# ase_flap.net
KiCad netlist of a schematic drawn in Altium Designer
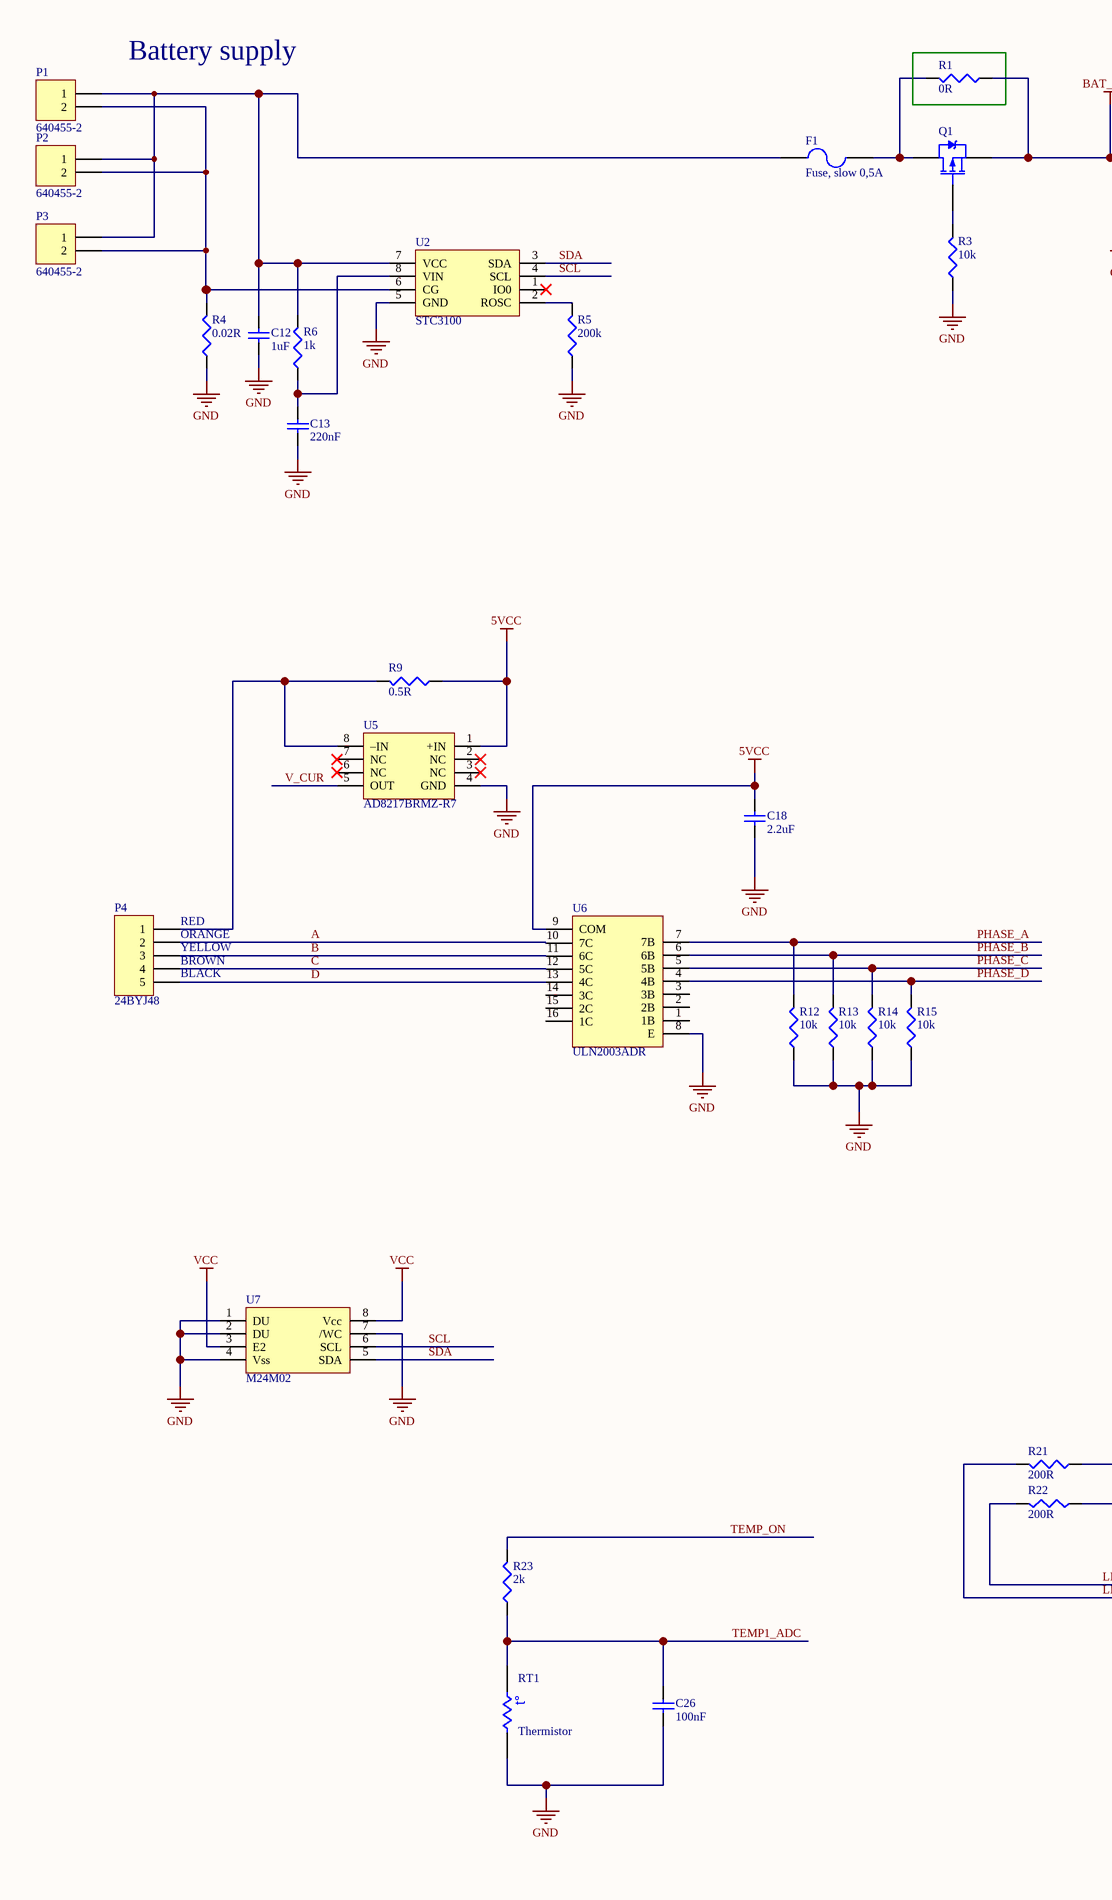
[diagram p0: ase_flap.SchDoc, left]
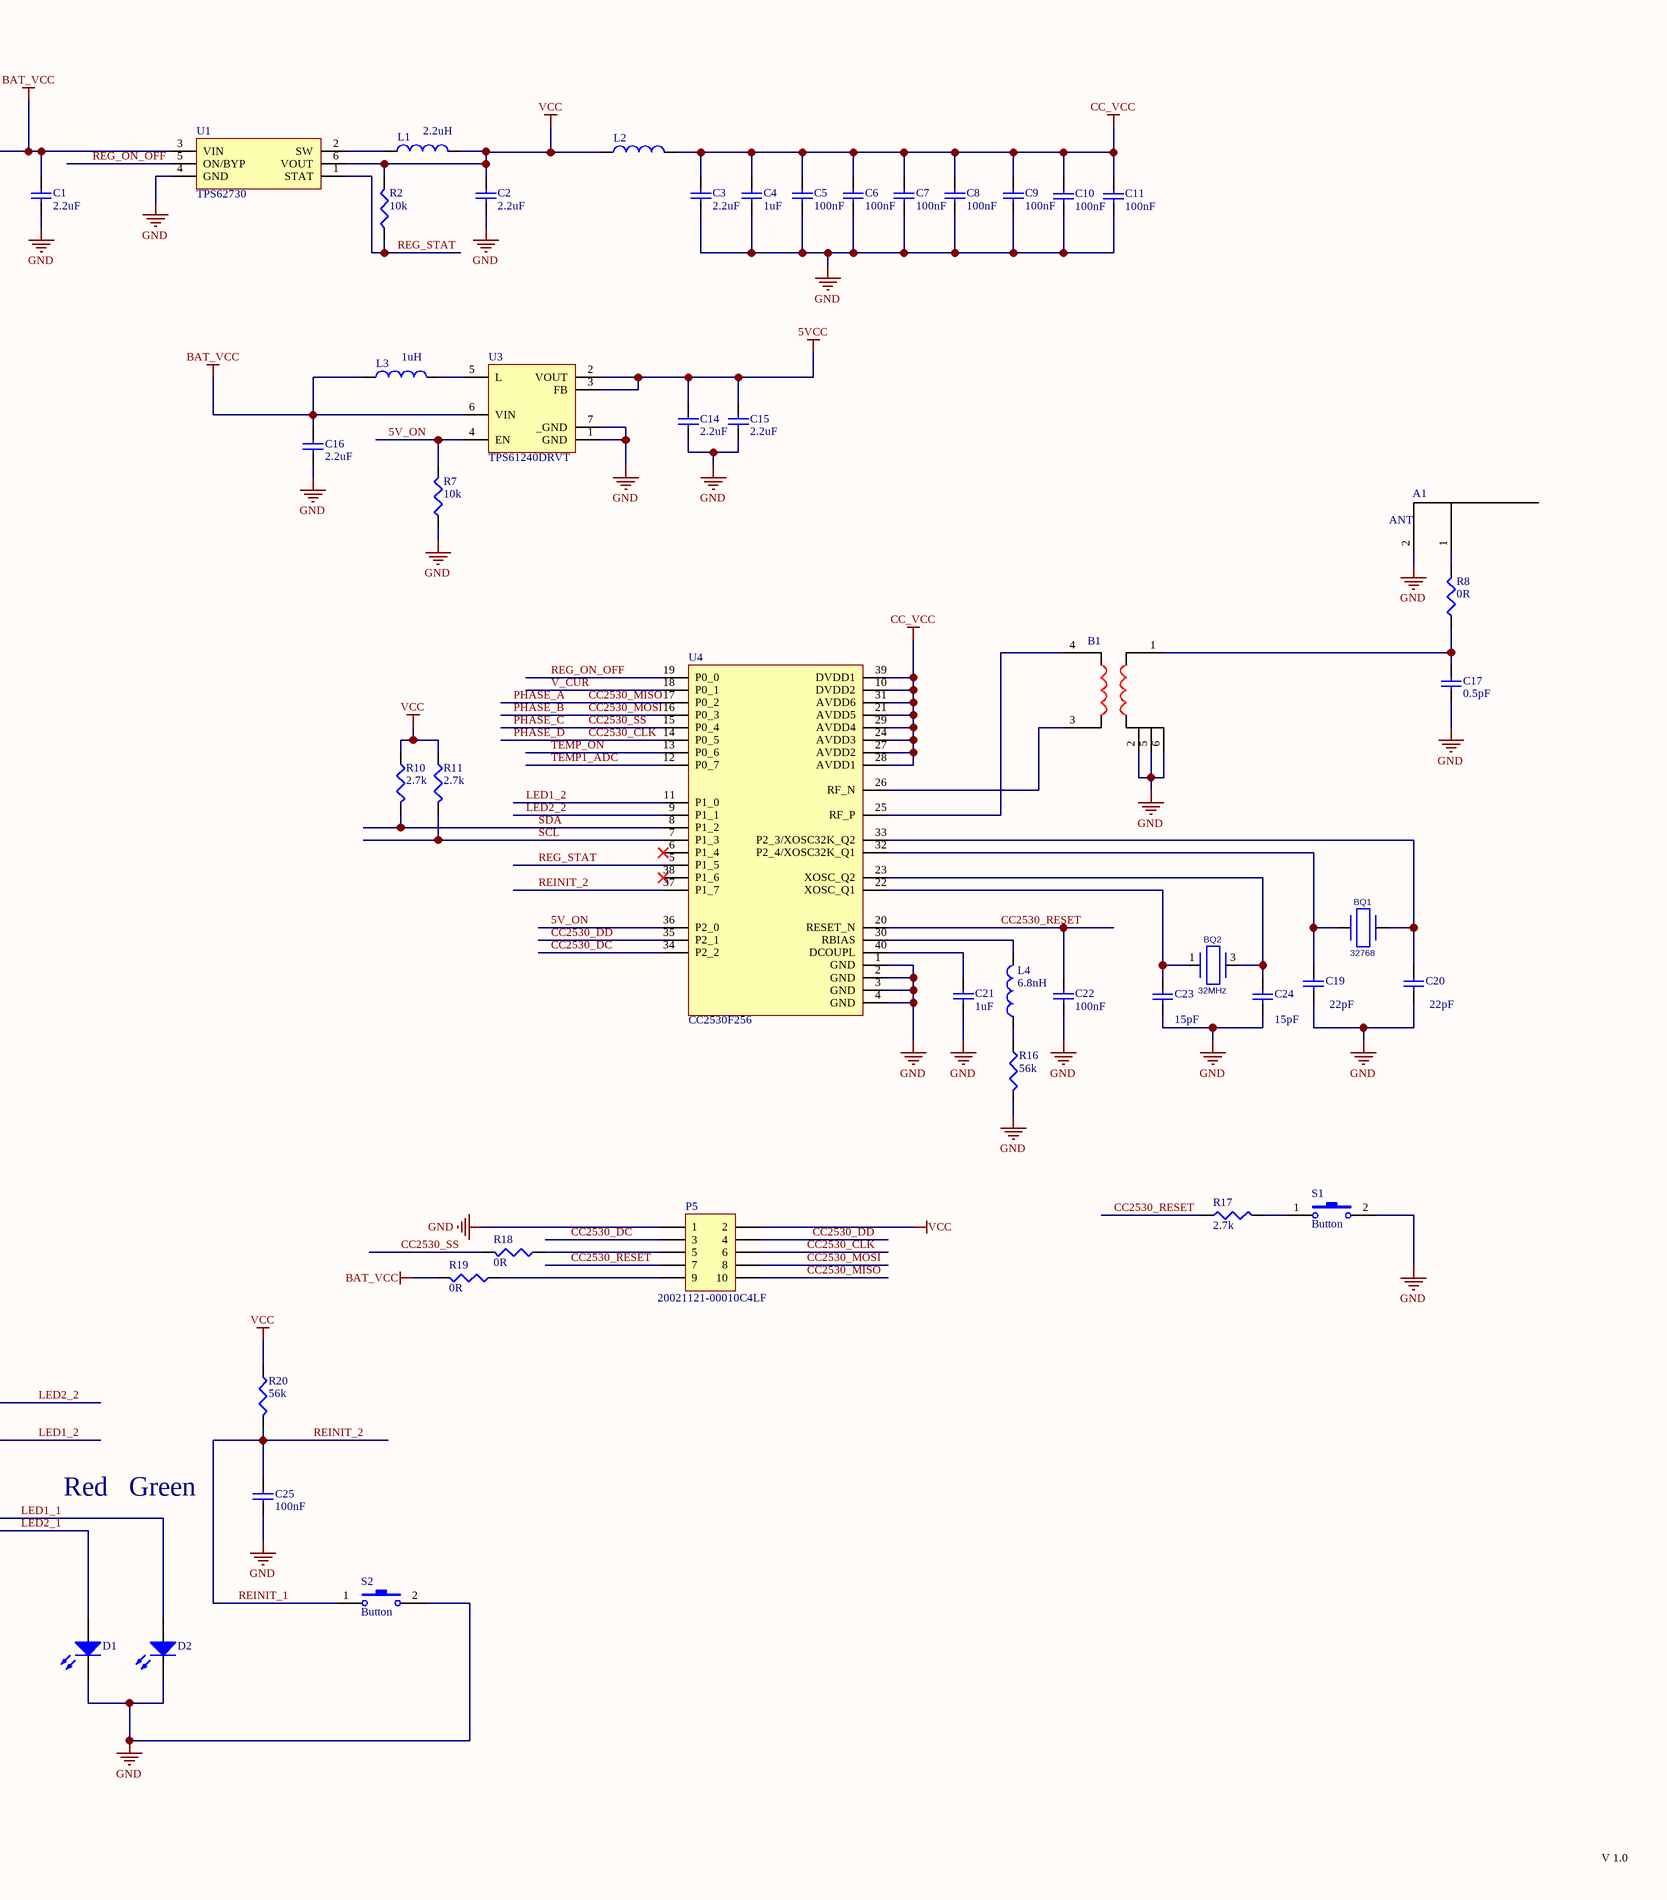
[diagram p1: ase_flap.SchDoc, right]

(export (version "E")
  (design (tool "Eeschema 10.0.6"))
  (components
    (comp (ref "A1")
      (value "ANT")
      (footprint "F ant")
      (description "Inverted-F Antenna")
      (fields (field (name "MANUFACTURER PART NUMBER") "PCB ANT"))
      (libsource (lib "CC25xx") (part "ANT"))
    )
    (comp (ref "B1")
      (value "BALUN")
      (footprint "2450BM15A0002")
      (description "BALUN JTI MATCHED ZIGBEE")
      (fields
        (field (name "MANUFACTURER PART NUMBER") "2450BM15A0002E")
        (field (name "MANUFACTURER") "Johanson Technology Inc")
      )
      (libsource (lib "CC25xx") (part "BALUN"))
    )
    (comp (ref "BQ1")
      (value "32768")
      (footprint "FC-12M")
      (description "CRYSTAL 32.768KHZ 12.5PF SMD")
      (fields
        (field (name "MANUFACTURER PART NUMBER") "FC-12M 32.7680KA-A3")
        (field (name "MANUFACTURER") "EPSON")
      )
      (libsource (lib "*") (part "6LC{colon}308C"))
    )
    (comp (ref "BQ2")
      (value "32MHz")
      (footprint "403C11A32M00000")
      (description "CRYSTAL 32MHZ 10PF SMD")
      (fields
        (field (name "MANUFACTURER PART NUMBER") "403C11A32M00000")
        (field (name "MANUFACTURER") "CTS-Frequency Controls")
      )
      (libsource (lib "*") (part "HC-49SMD"))
    )
    (comp (ref "C1")
      (value "2.2uF")
      (footprint "0402")
      (description "CAP CER 2.2UF 6.3V 20% X5R 0402")
      (fields
        (field (name "MANUFACTURER PART NUMBER") "CL05A225MQ5NNNC")
        (field (name "MANUFACTURER") "Samsung Electro-Mechanics America, Inc")
      )
      (libsource (lib "Miscellaneous Devices") (part "Cap"))
    )
    (comp (ref "C2")
      (value "2.2uF")
      (footprint "0402")
      (description "CAP CER 2.2UF 6.3V 20% X5R 0402")
      (fields
        (field (name "MANUFACTURER PART NUMBER") "CL05A225MQ5NNNC")
        (field (name "MANUFACTURER") "Samsung Electro-Mechanics America, Inc")
      )
      (libsource (lib "Miscellaneous Devices") (part "Cap"))
    )
    (comp (ref "C3")
      (value "2.2uF")
      (footprint "0402")
      (description "CAP CER 2.2UF 6.3V 20% X5R 0402")
      (fields
        (field (name "MANUFACTURER PART NUMBER") "CL05A225MQ5NNNC")
        (field (name "MANUFACTURER") "Samsung Electro-Mechanics America, Inc")
      )
      (libsource (lib "Miscellaneous Devices") (part "Cap"))
    )
    (comp (ref "C4")
      (value "1uF")
      (footprint "0402")
      (description "CAP CER 1UF 6.3V 10% X5R 0402")
      (fields
        (field (name "MANUFACTURER PART NUMBER") "GRM155R60J105KE19D")
        (field (name "MANUFACTURER") "Murata Electronics North America")
      )
      (libsource (lib "Miscellaneous Devices") (part "Cap"))
    )
    (comp (ref "C5")
      (value "100nF")
      (footprint "0402")
      (description "CAP CER 0.1UF 10V 20% X5R 0402")
      (fields
        (field (name "MANUFACTURER PART NUMBER") "CL05A104MP5NNNC")
        (field (name "MANUFACTURER") "Samsung Electro-Mechanics America, Inc")
      )
      (libsource (lib "Miscellaneous Devices") (part "Cap"))
    )
    (comp (ref "C6")
      (value "100nF")
      (footprint "0402")
      (description "CAP CER 0.1UF 10V 20% X5R 0402")
      (fields
        (field (name "MANUFACTURER PART NUMBER") "CL05A104MP5NNNC")
        (field (name "MANUFACTURER") "Samsung Electro-Mechanics America, Inc")
      )
      (libsource (lib "Miscellaneous Devices") (part "Cap"))
    )
    (comp (ref "C7")
      (value "100nF")
      (footprint "0402")
      (description "CAP CER 0.1UF 10V 20% X5R 0402")
      (fields
        (field (name "MANUFACTURER PART NUMBER") "CL05A104MP5NNNC")
        (field (name "MANUFACTURER") "Samsung Electro-Mechanics America, Inc")
      )
      (libsource (lib "Miscellaneous Devices") (part "Cap"))
    )
    (comp (ref "C8")
      (value "100nF")
      (footprint "0402")
      (description "CAP CER 0.1UF 10V 20% X5R 0402")
      (fields
        (field (name "MANUFACTURER PART NUMBER") "CL05A104MP5NNNC")
        (field (name "MANUFACTURER") "Samsung Electro-Mechanics America, Inc")
      )
      (libsource (lib "Miscellaneous Devices") (part "Cap"))
    )
    (comp (ref "C9")
      (value "100nF")
      (footprint "0402")
      (description "CAP CER 0.1UF 10V 20% X5R 0402")
      (fields
        (field (name "MANUFACTURER PART NUMBER") "CL05A104MP5NNNC")
        (field (name "MANUFACTURER") "Samsung Electro-Mechanics America, Inc")
      )
      (libsource (lib "Miscellaneous Devices") (part "Cap"))
    )
    (comp (ref "C10")
      (value "100nF")
      (footprint "0402")
      (description "CAP CER 0.1UF 10V 20% X5R 0402")
      (fields
        (field (name "MANUFACTURER PART NUMBER") "CL05A104MP5NNNC")
        (field (name "MANUFACTURER") "Samsung Electro-Mechanics America, Inc")
      )
      (libsource (lib "Miscellaneous Devices") (part "Cap"))
    )
    (comp (ref "C11")
      (value "100nF")
      (footprint "0402")
      (description "CAP CER 0.1UF 10V 20% X5R 0402")
      (fields
        (field (name "MANUFACTURER PART NUMBER") "CL05A104MP5NNNC")
        (field (name "MANUFACTURER") "Samsung Electro-Mechanics America, Inc")
      )
      (libsource (lib "Miscellaneous Devices") (part "Cap"))
    )
    (comp (ref "C12")
      (value "1uF")
      (footprint "0402")
      (description "CAP CER 1UF 6.3V 10% X5R 0402")
      (fields
        (field (name "MANUFACTURER PART NUMBER") "GRM155R60J105KE19D")
        (field (name "MANUFACTURER") "Murata Electronics North America")
      )
      (libsource (lib "Miscellaneous Devices") (part "Cap"))
    )
    (comp (ref "C13")
      (value "220nF")
      (footprint "0402")
      (description "CAP CER 0.22UF 10V 10% X5R 0402")
      (fields
        (field (name "MANUFACTURER PART NUMBER") "CL05A224KP5NNNC")
        (field (name "MANUFACTURER") "Samsung Electro-Mechanics America, Inc")
      )
      (libsource (lib "Miscellaneous Devices") (part "Cap"))
    )
    (comp (ref "C14")
      (value "2.2uF")
      (footprint "0402")
      (description "CAP CER 2.2UF 6.3V 20% X5R 0402")
      (fields
        (field (name "MANUFACTURER PART NUMBER") "CL05A225MQ5NNNC")
        (field (name "MANUFACTURER") "Samsung Electro-Mechanics America, Inc")
      )
      (libsource (lib "Miscellaneous Devices") (part "Cap"))
    )
    (comp (ref "C15")
      (value "2.2uF")
      (footprint "0402")
      (description "CAP CER 2.2UF 6.3V 20% X5R 0402")
      (fields
        (field (name "MANUFACTURER PART NUMBER") "CL05A225MQ5NNNC")
        (field (name "MANUFACTURER") "Samsung Electro-Mechanics America, Inc")
      )
      (libsource (lib "Miscellaneous Devices") (part "Cap"))
    )
    (comp (ref "C16")
      (value "2.2uF")
      (footprint "0402")
      (description "CAP CER 2.2UF 6.3V 20% X5R 0402")
      (fields
        (field (name "MANUFACTURER PART NUMBER") "CL05A225MQ5NNNC")
        (field (name "MANUFACTURER") "Samsung Electro-Mechanics America, Inc")
      )
      (libsource (lib "Miscellaneous Devices") (part "Cap"))
    )
    (comp (ref "C17")
      (value "0.5pF")
      (footprint "0402")
      (description "CAP CER 0.5PF 50V NP0 0402")
      (fields
        (field (name "MANUFACTURER PART NUMBER") "GRM1555C1HR50CA01D")
        (field (name "MANUFACTURER") "Murata Electronics North America")
      )
      (libsource (lib "Miscellaneous Devices") (part "Cap"))
    )
    (comp (ref "C18")
      (value "2.2uF")
      (footprint "0402")
      (description "CAP CER 2.2UF 6.3V 20% X5R 0402")
      (fields
        (field (name "MANUFACTURER PART NUMBER") "CL05A225MQ5NNNC")
        (field (name "MANUFACTURER") "Samsung Electro-Mechanics America, Inc")
      )
      (libsource (lib "Miscellaneous Devices") (part "Cap"))
    )
    (comp (ref "C19")
      (value "22pF")
      (footprint "0402")
      (description "CAP CER 22PF 50V 5% NP0 0402")
      (fields
        (field (name "MANUFACTURER PART NUMBER") "GRM1555C1H220JA01D")
        (field (name "MANUFACTURER") "Murata Electronics North America")
      )
      (libsource (lib "Miscellaneous Devices") (part "Cap"))
    )
    (comp (ref "C20")
      (value "22pF")
      (footprint "0402")
      (description "CAP CER 22PF 50V 5% NP0 0402")
      (fields
        (field (name "MANUFACTURER PART NUMBER") "GRM1555C1H220JA01D")
        (field (name "MANUFACTURER") "Murata Electronics North America")
      )
      (libsource (lib "Miscellaneous Devices") (part "Cap"))
    )
    (comp (ref "C21")
      (value "1uF")
      (footprint "0402")
      (description "CAP CER 1UF 6.3V 10% X5R 0402")
      (fields
        (field (name "MANUFACTURER PART NUMBER") "GRM155R60J105KE19D")
        (field (name "MANUFACTURER") "Murata Electronics North America")
      )
      (libsource (lib "Miscellaneous Devices") (part "Cap"))
    )
    (comp (ref "C22")
      (value "100nF")
      (footprint "0402")
      (description "CAP CER 0.1UF 10V 20% X5R 0402")
      (fields
        (field (name "MANUFACTURER PART NUMBER") "CL05A104MP5NNNC")
        (field (name "MANUFACTURER") "Samsung Electro-Mechanics America, Inc")
      )
      (libsource (lib "Miscellaneous Devices") (part "Cap"))
    )
    (comp (ref "C23")
      (value "15pF")
      (footprint "0402")
      (description "CAP CER 15PF 50V 5% NP0 0402")
      (fields
        (field (name "MANUFACTURER PART NUMBER") "GRM1555C1H150JA01D")
        (field (name "MANUFACTURER") "Murata Electronics North America")
      )
      (libsource (lib "Miscellaneous Devices") (part "Cap"))
    )
    (comp (ref "C24")
      (value "15pF")
      (footprint "0402")
      (description "CAP CER 15PF 50V 5% NP0 0402")
      (fields
        (field (name "MANUFACTURER PART NUMBER") "GRM1555C1H150JA01D")
        (field (name "MANUFACTURER") "Murata Electronics North America")
      )
      (libsource (lib "Miscellaneous Devices") (part "Cap"))
    )
    (comp (ref "C25")
      (value "100nF")
      (footprint "0402")
      (description "CAP CER 0.1UF 10V 20% X5R 0402")
      (fields
        (field (name "MANUFACTURER PART NUMBER") "CL05A104MP5NNNC")
        (field (name "MANUFACTURER") "Samsung Electro-Mechanics America, Inc")
      )
      (libsource (lib "Miscellaneous Devices") (part "Cap"))
    )
    (comp (ref "C26")
      (value "100nF")
      (footprint "0402")
      (description "CAP CER 0.1UF 10V 20% X5R 0402")
      (fields
        (field (name "MANUFACTURER PART NUMBER") "CL05A104MP5NNNC")
        (field (name "MANUFACTURER") "Samsung Electro-Mechanics America, Inc")
      )
      (libsource (lib "Miscellaneous Devices") (part "Cap"))
    )
    (comp (ref "D1")
      (value "Led")
      (footprint "LED0603")
      (description "LED SUPER RED CLEAR 0603 SMD")
      (fields
        (field (name "MANUFACTURER PART NUMBER") "LTST-C190KRKT")
        (field (name "MANUFACTURER") "Lite-On Inc")
      )
      (libsource (lib "Miscellaneous Devices") (part "LED0"))
    )
    (comp (ref "D2")
      (value "Led")
      (footprint "LED0603")
      (description "LED GREEN CLEAR THIN 0603 SMD")
      (fields
        (field (name "MANUFACTURER PART NUMBER") "LTST-C191KGKT")
        (field (name "MANUFACTURER") "Lite-On Inc")
      )
      (libsource (lib "Miscellaneous Devices") (part "LED0"))
    )
    (comp (ref "F1")
      (value "Fuse, slow 0,5A")
      (footprint "SF1206S0502")
      (description "FUSE 0,5A 63V 1206 SLOW")
      (fields
        (field (name "MANUFACTURER PART NUMBER") "SF-1206S050-2")
        (field (name "MANUFACTURER") "Bourns Inc.")
      )
      (libsource (lib "Miscellaneous Devices") (part "Fuse 2"))
    )
    (comp (ref "L1")
      (value "2.2uH")
      (footprint "6-0805_L")
      (description "INDUCTOR 2.2UH 0805")
      (fields
        (field (name "MANUFACTURER PART NUMBER") "LQM21PN2R2NGCD")
        (field (name "MANUFACTURER") "Murata Electronics North America")
      )
      (libsource (lib "Miscellaneous Devices") (part "Inductor"))
    )
    (comp (ref "L2")
      (value "Inductor")
      (footprint "0402")
      (description "FILTER CHIP 1000 OHM 250MA 0402")
      (fields
        (field (name "MANUFACTURER PART NUMBER") "BLM15HG102SN1D")
        (field (name "MANUFACTURER") "Murata Electronics North America")
      )
      (libsource (lib "Miscellaneous Devices") (part "Inductor"))
    )
    (comp (ref "L3")
      (value "1uH")
      (footprint "1008")
      (description "INDUCTOR POWER 1UH 2.2A 1008")
      (fields
        (field (name "MANUFACTURER PART NUMBER") "CIG22E1R0MNE")
        (field (name "MANUFACTURER") "Samsung Electro-Mechanics America, Inc")
      )
      (libsource (lib "Miscellaneous Devices") (part "Inductor"))
    )
    (comp (ref "L4")
      (value "6.8nH")
      (footprint "0402")
      (description "INDUCTOR 6.8NH 300MA 0402")
      (fields
        (field (name "MANUFACTURER PART NUMBER") "LQG15HS6N8J02D")
        (field (name "MANUFACTURER") "Murata Electronics North America")
      )
      (libsource (lib "Miscellaneous Devices") (part "Inductor"))
    )
    (comp (ref "P1")
      (value "Connector")
      (footprint "BAT_CON")
      (description "CONN HEADER VERT 2POS .100 TIN")
      (fields
        (field (name "MANUFACTURER PART NUMBER") "640455-2")
        (field (name "MANUFACTURER") "TE Connectivity")
      )
      (libsource (lib "Miscellaneous Connectors") (part "Header 2"))
    )
    (comp (ref "P2")
      (value "Connector")
      (footprint "BAT_CON")
      (description "CONN HEADER VERT 2POS .100 TIN")
      (fields
        (field (name "MANUFACTURER PART NUMBER") "640455-2")
        (field (name "MANUFACTURER") "TE Connectivity")
      )
      (libsource (lib "Miscellaneous Connectors") (part "Header 2"))
    )
    (comp (ref "P3")
      (value "Connector")
      (footprint "BAT_CON")
      (description "CONN HEADER VERT 2POS .100 TIN")
      (fields
        (field (name "MANUFACTURER PART NUMBER") "640455-2")
        (field (name "MANUFACTURER") "TE Connectivity")
      )
      (libsource (lib "Miscellaneous Connectors") (part "Header 2"))
    )
    (comp (ref "P4")
      (value "24BYJ48")
      (footprint "HDR1X5H")
      (description "Header, 5-Pin, Right Angle")
      (fields (field (name "MANUFACTURER PART NUMBER") "68016-205HLF") (field (name "MANUFACTURER") "FCI"))
      (libsource (lib "Miscellaneous Connectors") (part "Header 5H"))
    )
    (comp (ref "P5")
      (value "*")
      (footprint "20021121-00010C4LF")
      (description "CONN HEADER 10POS DL UNSHRD SMD")
      (fields
        (field (name "MANUFACTURER PART NUMBER") "20021121-00010C4LF")
        (field (name "MANUFACTURER") "FCI")
      )
      (libsource (lib "Miscellaneous Connectors") (part "Header 5X2"))
    )
    (comp (ref "Q1")
      (value "IRLML6302GTRPBF")
      (footprint "SOT-23_N")
      (description "HEXFET Power MOSFET")
      (fields
        (field (name "MANUFACTURER") "International Rectifier")
        (field (name "PUBLISHER") "Altium Limited")
      )
      (libsource (lib "IR Discrete MOSFET - Power") (part "IRLML6302"))
    )
    (comp (ref "R1")
      (value "0R")
      (footprint "0402")
      (description "RES 0.0 OHM 1/10W JUMP 0402 SMD")
      (fields
        (field (name "MANUFACTURER PART NUMBER") "ERJ-2GE0R00X")
        (field (name "MANUFACTURER") "Panasonic Electronic Components")
      )
      (libsource (lib "Miscellaneous Devices") (part "Res3"))
    )
    (comp (ref "R2")
      (value "10k")
      (footprint "0402")
      (description "RES 10K OHM 1/10W 5% 0402 SMD")
      (fields
        (field (name "MANUFACTURER PART NUMBER") "ERJ-2GEJ103X")
        (field (name "MANUFACTURER") "Panasonic Electronic Components")
      )
      (libsource (lib "Miscellaneous Devices") (part "Res3"))
    )
    (comp (ref "R3")
      (value "10k")
      (footprint "0402")
      (description "RES 10K OHM 1/10W 5% 0402 SMD")
      (fields
        (field (name "MANUFACTURER PART NUMBER") "ERJ-2GEJ103X")
        (field (name "MANUFACTURER") "Panasonic Electronic Components")
      )
      (libsource (lib "Miscellaneous Devices") (part "Res3"))
    )
    (comp (ref "R4")
      (value "0.02R")
      (footprint "0603")
      (description "RES 0.02 OHM 1/4W 1% 0603")
      (fields
        (field (name "MANUFACTURER PART NUMBER") "RU1608FR020CS")
        (field (name "MANUFACTURER") "Samsung Electro-Mechanics America, Inc")
      )
      (libsource (lib "Miscellaneous Devices") (part "Res3"))
    )
    (comp (ref "R5")
      (value "200k")
      (footprint "6-0805_L")
      (description "RES 200K OHM 1/8W .1% 0805 SMD")
      (fields
        (field (name "MANUFACTURER PART NUMBER") "ERA-6AEB204V")
        (field (name "MANUFACTURER") "Panasonic Electronic Components")
      )
      (libsource (lib "Miscellaneous Devices") (part "Res3"))
    )
    (comp (ref "R6")
      (value "1k")
      (footprint "0402")
      (description "RES 1K OHM 1/10W 1% 0402 SMD")
      (fields
        (field (name "MANUFACTURER PART NUMBER") "ERJ-2RKF1001X")
        (field (name "MANUFACTURER") "Panasonic Electronic Components")
      )
      (libsource (lib "Miscellaneous Devices") (part "Res3"))
    )
    (comp (ref "R7")
      (value "10k")
      (footprint "0402")
      (description "RES 10K OHM 1/10W 5% 0402 SMD")
      (fields
        (field (name "MANUFACTURER PART NUMBER") "ERJ-2GEJ103X")
        (field (name "MANUFACTURER") "Panasonic Electronic Components")
      )
      (libsource (lib "Miscellaneous Devices") (part "Res3"))
    )
    (comp (ref "R8")
      (value "0R")
      (footprint "0402")
      (description "RES 0.0 OHM 1/10W JUMP 0402 SMD")
      (fields
        (field (name "MANUFACTURER PART NUMBER") "ERJ-2GE0R00X")
        (field (name "MANUFACTURER") "Panasonic Electronic Components")
      )
      (libsource (lib "Miscellaneous Devices") (part "Res3"))
    )
    (comp (ref "R9")
      (value "0.5R")
      (footprint "0402")
      (description "RES 0.5 OHM 1/16W 1% 0402 SMD")
      (fields
        (field (name "MANUFACTURER PART NUMBER") "RL0402FR-070R5L")
        (field (name "MANUFACTURER") "Yageo")
      )
      (libsource (lib "Miscellaneous Devices") (part "Res3"))
    )
    (comp (ref "R10")
      (value "2.7k")
      (footprint "0402")
      (description "RES 2.7K OHM 1/10W 5% 0402 SMD")
      (fields
        (field (name "MANUFACTURER PART NUMBER") "ERJ-2GEJ272X")
        (field (name "MANUFACTURER") "Panasonic Electronic Components")
      )
      (libsource (lib "Miscellaneous Devices") (part "Res3"))
    )
    (comp (ref "R11")
      (value "2.7k")
      (footprint "0402")
      (description "RES 2.7K OHM 1/10W 5% 0402 SMD")
      (fields
        (field (name "MANUFACTURER PART NUMBER") "ERJ-2GEJ272X")
        (field (name "MANUFACTURER") "Panasonic Electronic Components")
      )
      (libsource (lib "Miscellaneous Devices") (part "Res3"))
    )
    (comp (ref "R12")
      (value "10k")
      (footprint "0402")
      (description "RES 10K OHM 1/10W 5% 0402 SMD")
      (fields
        (field (name "MANUFACTURER PART NUMBER") "ERJ-2GEJ103X")
        (field (name "MANUFACTURER") "Panasonic Electronic Components")
      )
      (libsource (lib "Miscellaneous Devices") (part "Res3"))
    )
    (comp (ref "R13")
      (value "10k")
      (footprint "0402")
      (description "RES 10K OHM 1/10W 5% 0402 SMD")
      (fields
        (field (name "MANUFACTURER PART NUMBER") "ERJ-2GEJ103X")
        (field (name "MANUFACTURER") "Panasonic Electronic Components")
      )
      (libsource (lib "Miscellaneous Devices") (part "Res3"))
    )
    (comp (ref "R14")
      (value "10k")
      (footprint "0402")
      (description "RES 10K OHM 1/10W 5% 0402 SMD")
      (fields
        (field (name "MANUFACTURER PART NUMBER") "ERJ-2GEJ103X")
        (field (name "MANUFACTURER") "Panasonic Electronic Components")
      )
      (libsource (lib "Miscellaneous Devices") (part "Res3"))
    )
    (comp (ref "R15")
      (value "10k")
      (footprint "0402")
      (description "RES 10K OHM 1/10W 5% 0402 SMD")
      (fields
        (field (name "MANUFACTURER PART NUMBER") "ERJ-2GEJ103X")
        (field (name "MANUFACTURER") "Panasonic Electronic Components")
      )
      (libsource (lib "Miscellaneous Devices") (part "Res3"))
    )
    (comp (ref "R16")
      (value "56k")
      (footprint "0402")
      (description "RES 56K OHM 1/10W 1% 0402 SMD")
      (fields
        (field (name "MANUFACTURER PART NUMBER") "ERJ-2RKF5602X")
        (field (name "MANUFACTURER") "Panasonic Electronic Components")
      )
      (libsource (lib "Miscellaneous Devices") (part "Res3"))
    )
    (comp (ref "R17")
      (value "2.7k")
      (footprint "0402")
      (description "RES 2.7K OHM 1/10W 5% 0402 SMD")
      (fields
        (field (name "MANUFACTURER PART NUMBER") "ERJ-2GEJ272X")
        (field (name "MANUFACTURER") "Panasonic Electronic Components")
      )
      (libsource (lib "Miscellaneous Devices") (part "Res3"))
    )
    (comp (ref "R18")
      (value "0R")
      (footprint "0402")
      (description "RES 0.0 OHM 1/10W JUMP 0402 SMD")
      (fields
        (field (name "MANUFACTURER PART NUMBER") "ERJ-2GE0R00X")
        (field (name "MANUFACTURER") "Panasonic Electronic Components")
      )
      (libsource (lib "Miscellaneous Devices") (part "Res3"))
    )
    (comp (ref "R19")
      (value "0R")
      (footprint "0402")
      (description "RES 0.0 OHM 1/10W JUMP 0402 SMD")
      (fields
        (field (name "MANUFACTURER PART NUMBER") "ERJ-2GE0R00X")
        (field (name "MANUFACTURER") "Panasonic Electronic Components")
      )
      (libsource (lib "Miscellaneous Devices") (part "Res3"))
    )
    (comp (ref "R20")
      (value "56k")
      (footprint "0402")
      (description "RES 56K OHM 1/10W 1% 0402 SMD")
      (fields
        (field (name "MANUFACTURER PART NUMBER") "ERJ-2RKF5602X")
        (field (name "MANUFACTURER") "Panasonic Electronic Components")
      )
      (libsource (lib "Miscellaneous Devices") (part "Res3"))
    )
    (comp (ref "R21")
      (value "200R")
      (footprint "0603")
      (description "RES 200 OHM 1/10W 5% 0603 SMD")
      (fields
        (field (name "MANUFACTURER PART NUMBER") "RC0603JR-07200RL")
        (field (name "MANUFACTURER") "Yageo")
      )
      (libsource (lib "Miscellaneous Devices") (part "Res3"))
    )
    (comp (ref "R22")
      (value "200R")
      (footprint "0603")
      (description "RES 200 OHM 1/10W 5% 0603 SMD")
      (fields
        (field (name "MANUFACTURER PART NUMBER") "RC0603JR-07200RL")
        (field (name "MANUFACTURER") "Yageo")
      )
      (libsource (lib "Miscellaneous Devices") (part "Res3"))
    )
    (comp (ref "R23")
      (value "2k")
      (footprint "0603")
      (description "RES 2.0K OHM 1/10W 5% 0603 SMD")
      (fields
        (field (name "MANUFACTURER PART NUMBER") "RC0603JR-072KL")
        (field (name "MANUFACTURER") "Yageo")
      )
      (libsource (lib "Miscellaneous Devices") (part "Res3"))
    )
    (comp (ref "RT1")
      (value "Thermistor")
      (footprint "0603")
      (description "THERMISTOR NTC 1K OHM 5% 0603")
      (fields
        (field (name "MANUFACTURER PART NUMBER") "ERT-J1VT102J")
        (field (name "MANUFACTURER") "Panasonic Electronic Components")
      )
      (libsource (lib "Miscellaneous Devices") (part "Res Thermal"))
    )
    (comp (ref "S1")
      (value "Button")
      (footprint "EVQP2402W")
      (description "SWITCH TACTILE SPST-NO 0.02A 15V")
      (fields
        (field (name "MANUFACTURER PART NUMBER") "EVQ-P2402W")
        (field (name "MANUFACTURER") "Panasonic Electronic Components")
      )
      (libsource (lib "Miscellaneous Devices") (part "SW-PB"))
    )
    (comp (ref "S2")
      (value "Button")
      (footprint "EVQP2402W")
      (description "SWITCH TACTILE SPST-NO 0.02A 15V")
      (fields
        (field (name "MANUFACTURER PART NUMBER") "EVQ-P2402W")
        (field (name "MANUFACTURER") "Panasonic Electronic Components")
      )
      (libsource (lib "Miscellaneous Devices") (part "SW-PB"))
    )
    (comp (ref "U1")
      (value "TPS62730")
      (footprint "6SON")
      (description "IC DCDC CONV STP-DN SYNC LP 6SON")
      (fields
        (field (name "MANUFACTURER PART NUMBER") "TPS62730DRYT")
        (field (name "MANUFACTURER") "Texas Instruments")
      )
      (libsource (lib "thermostat_main") (part "TPS62730"))
    )
    (comp (ref "U2")
      (value "STC3100")
      (footprint "DFN8")
      (description "IC BATTERY MON W/GAUGE 8-DFN")
      (fields
        (field (name "MANUFACTURER PART NUMBER") "STC3100IQT")
        (field (name "MANUFACTURER") "STMicroelectronics")
      )
      (libsource (lib "CC25xx") (part "STC3100"))
    )
    (comp (ref "U3")
      (value "TPS61240DRVT")
      (footprint "WSON6")
      (description "IC REG BOOST SYNC 5V 0.45A 6SON")
      (fields (field (name "MANUFACTURER") "Texas Instruments"))
      (libsource (lib "CC25xx") (part "TPS61240DRVT"))
    )
    (comp (ref "U4")
      (value "CC2530F256")
      (footprint "QFN40")
      (description "IC SOC IEEE 802.15.4/ZIG 40VQFN")
      (fields
        (field (name "MANUFACTURER PART NUMBER") "CC2530F256RHAT")
        (field (name "MANUFACTURER") "Texas Instruments")
      )
      (libsource (lib "CC25xx") (part "CC2530F256"))
    )
    (comp (ref "U5")
      (value "AD8217BRMZ-R7")
      (footprint "8MSOP")
      (description "IC CURRENT MONITOR HI SIDE 8MSOP")
      (fields (field (name "MANUFACTURER") "Analog Devices Inc"))
      (libsource (lib "CC25xx") (part "AD8217BRMZ-R7"))
    )
    (comp (ref "U6")
      (value "ULN2003ADR")
      (footprint "16SOIC")
      (description "TRANS 7 NPN DARL 50V 500MA 16SO")
      (fields (field (name "MANUFACTURER") "Texas Instruments"))
      (libsource (lib "CC25xx") (part "ULN2004ADR"))
    )
    (comp (ref "U7")
      (value "M24M02")
      (footprint "SO8")
      (description "IC EEPROM 2MBIT 1MHZ 8SO")
      (fields
        (field (name "MANUFACTURER PART NUMBER") "M24M02-DRMN6TP")
        (field (name "MANUFACTURER") "STMicroelectronics")
      )
      (libsource (lib "CC25xx") (part "M24M02"))
    )
  )
  (nets
    (net (code "1") (name "/5V_ON") (class "Default")
      (node (ref "R7") (pin "1") (pinfunction "1_1") (pintype "passive"))
      (node (ref "U3") (pin "4") (pinfunction "EN_4") (pintype "passive"))
      (node (ref "U4") (pin "36") (pinfunction "P2_0_36") (pintype "passive"))
    )
    (net (code "2") (name "/A") (class "Default")
      (node (ref "P4") (pin "2") (pinfunction "2_2") (pintype "passive"))
      (node (ref "U6") (pin "10") (pinfunction "7C_10") (pintype "passive"))
    )
    (net (code "3") (name "/B") (class "Default")
      (node (ref "P4") (pin "3") (pinfunction "3_3") (pintype "passive"))
      (node (ref "U6") (pin "11") (pinfunction "6C_11") (pintype "passive"))
    )
    (net (code "4") (name "/C") (class "Default")
      (node (ref "P4") (pin "4") (pinfunction "4_4") (pintype "passive"))
      (node (ref "U6") (pin "12") (pinfunction "5C_12") (pintype "passive"))
    )
    (net (code "5") (name "/CC2530_CLK") (class "Default")
      (node (ref "P5") (pin "6") (pinfunction "6_6") (pintype "passive"))
      (node (ref "R15") (pin "1") (pinfunction "1_1") (pintype "passive"))
      (node (ref "U4") (pin "14") (pinfunction "P0_5_14") (pintype "passive"))
      (node (ref "U6") (pin "4") (pinfunction "4B_4") (pintype "passive"))
    )
    (net (code "6") (name "/CC2530_DC") (class "Default")
      (node (ref "P5") (pin "3") (pinfunction "3_3") (pintype "passive"))
      (node (ref "U4") (pin "34") (pinfunction "P2_2_34") (pintype "passive"))
    )
    (net (code "7") (name "/CC2530_DD") (class "Default")
      (node (ref "P5") (pin "4") (pinfunction "4_4") (pintype "passive"))
      (node (ref "U4") (pin "35") (pinfunction "P2_1_35") (pintype "passive"))
    )
    (net (code "8") (name "/CC2530_MISO") (class "Default")
      (node (ref "P5") (pin "10") (pinfunction "10_10") (pintype "passive"))
      (node (ref "R12") (pin "1") (pinfunction "1_1") (pintype "passive"))
      (node (ref "U4") (pin "17") (pinfunction "P0_2_17") (pintype "passive"))
      (node (ref "U6") (pin "7") (pinfunction "7B_7") (pintype "passive"))
    )
    (net (code "9") (name "/CC2530_MOSI") (class "Default")
      (node (ref "P5") (pin "8") (pinfunction "8_8") (pintype "passive"))
      (node (ref "R13") (pin "1") (pinfunction "1_1") (pintype "passive"))
      (node (ref "U4") (pin "16") (pinfunction "P0_3_16") (pintype "passive"))
      (node (ref "U6") (pin "6") (pinfunction "6B_6") (pintype "passive"))
    )
    (net (code "10") (name "/CC2530_RESET") (class "Default")
      (node (ref "C22") (pin "1") (pinfunction "1_1") (pintype "passive"))
      (node (ref "P5") (pin "7") (pinfunction "7_7") (pintype "passive"))
      (node (ref "R17") (pin "2") (pinfunction "2_2") (pintype "passive"))
      (node (ref "U4") (pin "20") (pinfunction "RESET_N_20") (pintype "passive"))
    )
    (net (code "11") (name "/CC2530_SS") (class "Default")
      (node (ref "R14") (pin "1") (pinfunction "1_1") (pintype "passive"))
      (node (ref "R18") (pin "2") (pinfunction "2_2") (pintype "passive"))
      (node (ref "U4") (pin "15") (pinfunction "P0_4_15") (pintype "passive"))
      (node (ref "U6") (pin "5") (pinfunction "5B_5") (pintype "passive"))
    )
    (net (code "12") (name "/D") (class "Default")
      (node (ref "P4") (pin "5") (pinfunction "5_5") (pintype "passive"))
      (node (ref "U6") (pin "13") (pinfunction "4C_13") (pintype "passive"))
    )
    (net (code "13") (name "/LED1_1") (class "Default")
      (node (ref "D2") (pin "1") (pinfunction "A_1") (pintype "passive"))
      (node (ref "R22") (pin "1") (pinfunction "1_1") (pintype "passive"))
    )
    (net (code "14") (name "/LED1_2") (class "Default")
      (node (ref "R22") (pin "2") (pinfunction "2_2") (pintype "passive"))
      (node (ref "U4") (pin "11") (pinfunction "P1_0_11") (pintype "passive"))
    )
    (net (code "15") (name "/LED2_1") (class "Default")
      (node (ref "D1") (pin "1") (pinfunction "A_1") (pintype "passive"))
      (node (ref "R21") (pin "1") (pinfunction "1_1") (pintype "passive"))
    )
    (net (code "16") (name "/LED2_2") (class "Default")
      (node (ref "R21") (pin "2") (pinfunction "2_2") (pintype "passive"))
      (node (ref "U4") (pin "9") (pinfunction "P1_1_9") (pintype "passive"))
    )
    (net (code "17") (name "/REG_ON_OFF") (class "Default")
      (node (ref "U1") (pin "5") (pinfunction "ON/BYP_5") (pintype "passive"))
      (node (ref "U4") (pin "19") (pinfunction "P0_0_19") (pintype "passive"))
    )
    (net (code "18") (name "/REG_STAT") (class "Default")
      (node (ref "R2") (pin "2") (pinfunction "2_2") (pintype "passive"))
      (node (ref "U1") (pin "1") (pinfunction "STAT_1") (pintype "passive"))
      (node (ref "U4") (pin "5") (pinfunction "P1_5_5") (pintype "passive"))
    )
    (net (code "19") (name "/REINIT_1") (class "Default")
      (node (ref "C25") (pin "1") (pinfunction "1_1") (pintype "passive"))
      (node (ref "R20") (pin "2") (pinfunction "2_2") (pintype "passive"))
      (node (ref "S2") (pin "1") (pinfunction "1_1") (pintype "passive"))
      (node (ref "U4") (pin "37") (pinfunction "P1_7_37") (pintype "passive"))
    )
    (net (code "20") (name "/SCL") (class "Default")
      (node (ref "R11") (pin "1") (pinfunction "1_1") (pintype "passive"))
      (node (ref "U2") (pin "4") (pinfunction "SCL_4") (pintype "passive"))
      (node (ref "U4") (pin "7") (pinfunction "P1_3_7") (pintype "passive"))
      (node (ref "U7") (pin "6") (pinfunction "SCL_6") (pintype "passive"))
    )
    (net (code "21") (name "/SDA") (class "Default")
      (node (ref "R10") (pin "1") (pinfunction "1_1") (pintype "passive"))
      (node (ref "U2") (pin "3") (pinfunction "SDA_3") (pintype "passive"))
      (node (ref "U4") (pin "8") (pinfunction "P1_2_8") (pintype "passive"))
      (node (ref "U7") (pin "5") (pinfunction "SDA_5") (pintype "passive"))
    )
    (net (code "22") (name "/TEMP1_ADC") (class "Default")
      (node (ref "C26") (pin "1") (pinfunction "1_1") (pintype "passive"))
      (node (ref "R23") (pin "1") (pinfunction "1_1") (pintype "passive"))
      (node (ref "RT1") (pin "1") (pinfunction "1_1") (pintype "passive"))
      (node (ref "U4") (pin "12") (pinfunction "P0_7_12") (pintype "passive"))
    )
    (net (code "23") (name "/TEMP_ON") (class "Default")
      (node (ref "R23") (pin "2") (pinfunction "2_2") (pintype "passive"))
      (node (ref "U4") (pin "13") (pinfunction "P0_6_13") (pintype "passive"))
    )
    (net (code "24") (name "/V_CUR") (class "Default")
      (node (ref "U4") (pin "18") (pinfunction "P0_1_18") (pintype "passive"))
      (node (ref "U5") (pin "5") (pinfunction "OUT_5") (pintype "passive"))
    )
    (net (code "25") (name "5VCC") (class "Default")
      (node (ref "C14") (pin "1") (pinfunction "1_1") (pintype "passive"))
      (node (ref "C15") (pin "1") (pinfunction "1_1") (pintype "passive"))
      (node (ref "C18") (pin "1") (pinfunction "1_1") (pintype "passive"))
      (node (ref "R9") (pin "2") (pinfunction "2_2") (pintype "passive"))
      (node (ref "U3") (pin "2") (pinfunction "VOUT_2") (pintype "passive"))
      (node (ref "U3") (pin "3") (pinfunction "FB_3") (pintype "passive"))
      (node (ref "U5") (pin "1") (pinfunction "+IN_1") (pintype "passive"))
      (node (ref "U6") (pin "9") (pinfunction "COM_9") (pintype "passive"))
    )
    (net (code "26") (name "BAT_VCC") (class "Default")
      (node (ref "C1") (pin "1") (pinfunction "1_1") (pintype "passive"))
      (node (ref "C16") (pin "1") (pinfunction "1_1") (pintype "passive"))
      (node (ref "L3") (pin "1") (pinfunction "1_1") (pintype "passive"))
      (node (ref "Q1") (pin "2") (pinfunction "S_2") (pintype "passive"))
      (node (ref "R1") (pin "1") (pinfunction "1_1") (pintype "passive"))
      (node (ref "R19") (pin "2") (pinfunction "2_2") (pintype "passive"))
      (node (ref "U1") (pin "3") (pinfunction "VIN_3") (pintype "passive"))
      (node (ref "U3") (pin "6") (pinfunction "VIN_6") (pintype "passive"))
    )
    (net (code "27") (name "CC_VCC") (class "Default")
      (node (ref "C10") (pin "1") (pinfunction "1_1") (pintype "passive"))
      (node (ref "C11") (pin "1") (pinfunction "1_1") (pintype "passive"))
      (node (ref "C3") (pin "1") (pinfunction "1_1") (pintype "passive"))
      (node (ref "C4") (pin "1") (pinfunction "1_1") (pintype "passive"))
      (node (ref "C5") (pin "1") (pinfunction "1_1") (pintype "passive"))
      (node (ref "C6") (pin "1") (pinfunction "1_1") (pintype "passive"))
      (node (ref "C7") (pin "1") (pinfunction "1_1") (pintype "passive"))
      (node (ref "C8") (pin "1") (pinfunction "1_1") (pintype "passive"))
      (node (ref "C9") (pin "1") (pinfunction "1_1") (pintype "passive"))
      (node (ref "L2") (pin "2") (pinfunction "2_2") (pintype "passive"))
      (node (ref "U4") (pin "10") (pinfunction "DVDD2_10") (pintype "passive"))
      (node (ref "U4") (pin "21") (pinfunction "AVDD5_21") (pintype "passive"))
      (node (ref "U4") (pin "24") (pinfunction "AVDD3_24") (pintype "passive"))
      (node (ref "U4") (pin "27") (pinfunction "AVDD2_27") (pintype "passive"))
      (node (ref "U4") (pin "28") (pinfunction "AVDD1_28") (pintype "passive"))
      (node (ref "U4") (pin "29") (pinfunction "AVDD4_29") (pintype "passive"))
      (node (ref "U4") (pin "31") (pinfunction "AVDD6_31") (pintype "passive"))
      (node (ref "U4") (pin "39") (pinfunction "DVDD1_39") (pintype "passive"))
    )
    (net (code "28") (name "GND") (class "Default")
      (node (ref "A1") (pin "2") (pinfunction "2_2") (pintype "passive"))
      (node (ref "B1") (pin "2") (pinfunction "2_2") (pintype "passive"))
      (node (ref "B1") (pin "5") (pinfunction "5_5") (pintype "passive"))
      (node (ref "B1") (pin "6") (pinfunction "6_6") (pintype "passive"))
      (node (ref "C1") (pin "2") (pinfunction "2_2") (pintype "passive"))
      (node (ref "C10") (pin "2") (pinfunction "2_2") (pintype "passive"))
      (node (ref "C11") (pin "2") (pinfunction "2_2") (pintype "passive"))
      (node (ref "C12") (pin "2") (pinfunction "2_2") (pintype "passive"))
      (node (ref "C13") (pin "2") (pinfunction "2_2") (pintype "passive"))
      (node (ref "C14") (pin "2") (pinfunction "2_2") (pintype "passive"))
      (node (ref "C15") (pin "2") (pinfunction "2_2") (pintype "passive"))
      (node (ref "C16") (pin "2") (pinfunction "2_2") (pintype "passive"))
      (node (ref "C17") (pin "2") (pinfunction "2_2") (pintype "passive"))
      (node (ref "C18") (pin "2") (pinfunction "2_2") (pintype "passive"))
      (node (ref "C19") (pin "1") (pinfunction "1_1") (pintype "passive"))
      (node (ref "C2") (pin "2") (pinfunction "2_2") (pintype "passive"))
      (node (ref "C20") (pin "1") (pinfunction "1_1") (pintype "passive"))
      (node (ref "C21") (pin "2") (pinfunction "2_2") (pintype "passive"))
      (node (ref "C22") (pin "2") (pinfunction "2_2") (pintype "passive"))
      (node (ref "C23") (pin "1") (pinfunction "1_1") (pintype "passive"))
      (node (ref "C24") (pin "1") (pinfunction "1_1") (pintype "passive"))
      (node (ref "C25") (pin "2") (pinfunction "2_2") (pintype "passive"))
      (node (ref "C26") (pin "2") (pinfunction "2_2") (pintype "passive"))
      (node (ref "C3") (pin "2") (pinfunction "2_2") (pintype "passive"))
      (node (ref "C4") (pin "2") (pinfunction "2_2") (pintype "passive"))
      (node (ref "C5") (pin "2") (pinfunction "2_2") (pintype "passive"))
      (node (ref "C6") (pin "2") (pinfunction "2_2") (pintype "passive"))
      (node (ref "C7") (pin "2") (pinfunction "2_2") (pintype "passive"))
      (node (ref "C8") (pin "2") (pinfunction "2_2") (pintype "passive"))
      (node (ref "C9") (pin "2") (pinfunction "2_2") (pintype "passive"))
      (node (ref "D1") (pin "2") (pinfunction "K_2") (pintype "passive"))
      (node (ref "D2") (pin "2") (pinfunction "K_2") (pintype "passive"))
      (node (ref "P5") (pin "1") (pinfunction "1_1") (pintype "passive"))
      (node (ref "R12") (pin "2") (pinfunction "2_2") (pintype "passive"))
      (node (ref "R13") (pin "2") (pinfunction "2_2") (pintype "passive"))
      (node (ref "R14") (pin "2") (pinfunction "2_2") (pintype "passive"))
      (node (ref "R15") (pin "2") (pinfunction "2_2") (pintype "passive"))
      (node (ref "R16") (pin "2") (pinfunction "2_2") (pintype "passive"))
      (node (ref "R3") (pin "2") (pinfunction "2_2") (pintype "passive"))
      (node (ref "R4") (pin "2") (pinfunction "2_2") (pintype "passive"))
      (node (ref "R5") (pin "2") (pinfunction "2_2") (pintype "passive"))
      (node (ref "R7") (pin "2") (pinfunction "2_2") (pintype "passive"))
      (node (ref "RT1") (pin "2") (pinfunction "2_2") (pintype "passive"))
      (node (ref "S1") (pin "2") (pinfunction "2_2") (pintype "passive"))
      (node (ref "S2") (pin "2") (pinfunction "2_2") (pintype "passive"))
      (node (ref "U1") (pin "4") (pinfunction "GND_4") (pintype "passive"))
      (node (ref "U2") (pin "5") (pinfunction "GND_5") (pintype "passive"))
      (node (ref "U3") (pin "1") (pinfunction "GND_1") (pintype "passive"))
      (node (ref "U3") (pin "7") (pinfunction "_GND_7") (pintype "passive"))
      (node (ref "U4") (pin "1") (pinfunction "GND_1") (pintype "passive"))
      (node (ref "U4") (pin "2") (pinfunction "GND_2") (pintype "passive"))
      (node (ref "U4") (pin "3") (pinfunction "GND_3") (pintype "passive"))
      (node (ref "U4") (pin "4") (pinfunction "GND_4") (pintype "passive"))
      (node (ref "U5") (pin "4") (pinfunction "GND_4") (pintype "passive"))
      (node (ref "U6") (pin "8") (pinfunction "E_8") (pintype "passive"))
      (node (ref "U7") (pin "1") (pinfunction "DU_1") (pintype "passive"))
      (node (ref "U7") (pin "2") (pinfunction "DU_2") (pintype "passive"))
      (node (ref "U7") (pin "4") (pinfunction "Vss_4") (pintype "passive"))
      (node (ref "U7") (pin "7") (pinfunction "/WC_7") (pintype "passive"))
    )
    (net (code "29") (name "Net-(A1-Pad1)") (class "Default")
      (node (ref "A1") (pin "1") (pinfunction "1_1") (pintype "passive"))
      (node (ref "R8") (pin "2") (pinfunction "2_2") (pintype "passive"))
    )
    (net (code "30") (name "Net-(B1-Pad1)") (class "Default")
      (node (ref "B1") (pin "1") (pinfunction "1_1") (pintype "passive"))
      (node (ref "C17") (pin "1") (pinfunction "1_1") (pintype "passive"))
      (node (ref "R8") (pin "1") (pinfunction "1_1") (pintype "passive"))
    )
    (net (code "31") (name "Net-(L4-Pad1)") (class "Default")
      (node (ref "L4") (pin "1") (pinfunction "1_1") (pintype "passive"))
      (node (ref "R16") (pin "1") (pinfunction "1_1") (pintype "passive"))
    )
    (net (code "32") (name "Net-(P5-Pad5)") (class "Default")
      (node (ref "P5") (pin "5") (pinfunction "5_5") (pintype "passive"))
      (node (ref "R18") (pin "1") (pinfunction "1_1") (pintype "passive"))
    )
    (net (code "33") (name "Net-(P5-Pad9)") (class "Default")
      (node (ref "P5") (pin "9") (pinfunction "9_9") (pintype "passive"))
      (node (ref "R19") (pin "1") (pinfunction "1_1") (pintype "passive"))
    )
    (net (code "34") (name "Net-(Q1-D)") (class "Default")
      (node (ref "F1") (pin "2") (pinfunction "2_2") (pintype "passive"))
      (node (ref "Q1") (pin "3") (pinfunction "D_3") (pintype "passive"))
      (node (ref "R1") (pin "2") (pinfunction "2_2") (pintype "passive"))
    )
    (net (code "35") (name "Net-(Q1-G)") (class "Default")
      (node (ref "Q1") (pin "1") (pinfunction "G_1") (pintype "passive"))
      (node (ref "R3") (pin "1") (pinfunction "1_1") (pintype "passive"))
    )
    (net (code "36") (name "Net-(R17-Pad1)") (class "Default")
      (node (ref "R17") (pin "1") (pinfunction "1_1") (pintype "passive"))
      (node (ref "S1") (pin "1") (pinfunction "1_1") (pintype "passive"))
    )
    (net (code "37") (name "Net-(U1-SW)") (class "Default")
      (node (ref "L1") (pin "1") (pinfunction "1_1") (pintype "passive"))
      (node (ref "U1") (pin "2") (pinfunction "SW_2") (pintype "passive"))
    )
    (net (code "38") (name "Net-(U2-CG)") (class "Default")
      (node (ref "P1") (pin "2") (pinfunction "2_2") (pintype "passive"))
      (node (ref "P2") (pin "2") (pinfunction "2_2") (pintype "passive"))
      (node (ref "P3") (pin "2") (pinfunction "2_2") (pintype "passive"))
      (node (ref "R4") (pin "1") (pinfunction "1_1") (pintype "passive"))
      (node (ref "U2") (pin "6") (pinfunction "CG_6") (pintype "passive"))
    )
    (net (code "39") (name "Net-(U2-ROSC)") (class "Default")
      (node (ref "R5") (pin "1") (pinfunction "1_1") (pintype "passive"))
      (node (ref "U2") (pin "2") (pinfunction "ROSC_2") (pintype "passive"))
    )
    (net (code "40") (name "Net-(U2-VCC)") (class "Default")
      (node (ref "C12") (pin "1") (pinfunction "1_1") (pintype "passive"))
      (node (ref "F1") (pin "1") (pinfunction "1_1") (pintype "passive"))
      (node (ref "P1") (pin "1") (pinfunction "1_1") (pintype "passive"))
      (node (ref "P2") (pin "1") (pinfunction "1_1") (pintype "passive"))
      (node (ref "P3") (pin "1") (pinfunction "1_1") (pintype "passive"))
      (node (ref "R6") (pin "1") (pinfunction "1_1") (pintype "passive"))
      (node (ref "U2") (pin "7") (pinfunction "VCC_7") (pintype "passive"))
    )
    (net (code "41") (name "Net-(U2-VIN)") (class "Default")
      (node (ref "C13") (pin "1") (pinfunction "1_1") (pintype "passive"))
      (node (ref "R6") (pin "2") (pinfunction "2_2") (pintype "passive"))
      (node (ref "U2") (pin "8") (pinfunction "VIN_8") (pintype "passive"))
    )
    (net (code "42") (name "Net-(U3-L)") (class "Default")
      (node (ref "L3") (pin "2") (pinfunction "2_2") (pintype "passive"))
      (node (ref "U3") (pin "5") (pinfunction "L_5") (pintype "passive"))
    )
    (net (code "43") (name "Net-(U4-DCOUPL)") (class "Default")
      (node (ref "C21") (pin "1") (pinfunction "1_1") (pintype "passive"))
      (node (ref "U4") (pin "40") (pinfunction "DCOUPL_40") (pintype "passive"))
    )
    (net (code "44") (name "Net-(U4-P2_3{slash}XOSC32K_Q2)") (class "Default")
      (node (ref "BQ1") (pin "2") (pintype "passive"))
      (node (ref "C20") (pin "2") (pinfunction "2_2") (pintype "passive"))
      (node (ref "U4") (pin "33") (pinfunction "P2_3/XOSC32K_Q2_33") (pintype "passive"))
    )
    (net (code "45") (name "Net-(U4-P2_4{slash}XOSC32K_Q1)") (class "Default")
      (node (ref "BQ1") (pin "1") (pintype "passive"))
      (node (ref "C19") (pin "2") (pinfunction "2_2") (pintype "passive"))
      (node (ref "U4") (pin "32") (pinfunction "P2_4/XOSC32K_Q1_32") (pintype "passive"))
    )
    (net (code "46") (name "Net-(U4-RBIAS)") (class "Default")
      (node (ref "L4") (pin "2") (pinfunction "2_2") (pintype "passive"))
      (node (ref "U4") (pin "30") (pinfunction "RBIAS_30") (pintype "passive"))
    )
    (net (code "47") (name "Net-(U4-RF_N)") (class "Default")
      (node (ref "B1") (pin "3") (pinfunction "3_3") (pintype "passive"))
      (node (ref "U4") (pin "26") (pinfunction "RF_N_26") (pintype "passive"))
    )
    (net (code "48") (name "Net-(U4-RF_P)") (class "Default")
      (node (ref "B1") (pin "4") (pinfunction "4_4") (pintype "passive"))
      (node (ref "U4") (pin "25") (pinfunction "RF_P_25") (pintype "passive"))
    )
    (net (code "49") (name "Net-(U4-XOSC_Q1)") (class "Default")
      (node (ref "BQ2") (pin "1") (pintype "passive"))
      (node (ref "C23") (pin "2") (pinfunction "2_2") (pintype "passive"))
      (node (ref "U4") (pin "22") (pinfunction "XOSC_Q1_22") (pintype "passive"))
    )
    (net (code "50") (name "Net-(U4-XOSC_Q2)") (class "Default")
      (node (ref "BQ2") (pin "3") (pintype "passive"))
      (node (ref "C24") (pin "2") (pinfunction "2_2") (pintype "passive"))
      (node (ref "U4") (pin "23") (pinfunction "XOSC_Q2_23") (pintype "passive"))
    )
    (net (code "51") (name "Net-(U5-IN)") (class "Default")
      (node (ref "P4") (pin "1") (pinfunction "1_1") (pintype "passive"))
      (node (ref "R9") (pin "1") (pinfunction "1_1") (pintype "passive"))
      (node (ref "U5") (pin "8") (pinfunction "IN_8") (pintype "passive"))
    )
    (net (code "52") (name "VCC") (class "Default")
      (node (ref "C2") (pin "1") (pinfunction "1_1") (pintype "passive"))
      (node (ref "L1") (pin "2") (pinfunction "2_2") (pintype "passive"))
      (node (ref "L2") (pin "1") (pinfunction "1_1") (pintype "passive"))
      (node (ref "P5") (pin "2") (pinfunction "2_2") (pintype "passive"))
      (node (ref "R10") (pin "2") (pinfunction "2_2") (pintype "passive"))
      (node (ref "R11") (pin "2") (pinfunction "2_2") (pintype "passive"))
      (node (ref "R2") (pin "1") (pinfunction "1_1") (pintype "passive"))
      (node (ref "R20") (pin "1") (pinfunction "1_1") (pintype "passive"))
      (node (ref "U1") (pin "6") (pinfunction "VOUT_6") (pintype "passive"))
      (node (ref "U7") (pin "3") (pinfunction "E2_3") (pintype "passive"))
      (node (ref "U7") (pin "8") (pinfunction "Vcc_8") (pintype "passive"))
    )
    (net (code "53") (name "unconnected-(U2-IO0-Pad1)") (class "Default")
      (node (ref "U2") (pin "1") (pinfunction "IO0_1") (pintype "passive+no_connect"))
    )
    (net (code "54") (name "unconnected-(U4-P1_4-Pad6)") (class "Default")
      (node (ref "U4") (pin "6") (pinfunction "P1_4_6") (pintype "passive+no_connect"))
    )
    (net (code "55") (name "unconnected-(U4-P1_6-Pad38)") (class "Default")
      (node (ref "U4") (pin "38") (pinfunction "P1_6_38") (pintype "passive+no_connect"))
    )
    (net (code "56") (name "unconnected-(U5-NC-Pad2)") (class "Default")
      (node (ref "U5") (pin "2") (pinfunction "NC_2") (pintype "passive+no_connect"))
    )
    (net (code "57") (name "unconnected-(U5-NC-Pad3)") (class "Default")
      (node (ref "U5") (pin "3") (pinfunction "NC_3") (pintype "passive+no_connect"))
    )
    (net (code "58") (name "unconnected-(U5-NC-Pad6)") (class "Default")
      (node (ref "U5") (pin "6") (pinfunction "NC_6") (pintype "passive+no_connect"))
    )
    (net (code "59") (name "unconnected-(U5-NC-Pad7)") (class "Default")
      (node (ref "U5") (pin "7") (pinfunction "NC_7") (pintype "passive+no_connect"))
    )
    (net (code "60") (name "unconnected-(U6-1B-Pad1)") (class "Default")
      (node (ref "U6") (pin "1") (pinfunction "1B_1") (pintype "passive"))
    )
    (net (code "61") (name "unconnected-(U6-1C-Pad16)") (class "Default")
      (node (ref "U6") (pin "16") (pinfunction "1C_16") (pintype "passive"))
    )
    (net (code "62") (name "unconnected-(U6-2B-Pad2)") (class "Default")
      (node (ref "U6") (pin "2") (pinfunction "2B_2") (pintype "passive"))
    )
    (net (code "63") (name "unconnected-(U6-2C-Pad15)") (class "Default")
      (node (ref "U6") (pin "15") (pinfunction "2C_15") (pintype "passive"))
    )
    (net (code "64") (name "unconnected-(U6-3B-Pad3)") (class "Default")
      (node (ref "U6") (pin "3") (pinfunction "3B_3") (pintype "passive"))
    )
    (net (code "65") (name "unconnected-(U6-3C-Pad14)") (class "Default")
      (node (ref "U6") (pin "14") (pinfunction "3C_14") (pintype "passive"))
    )
  )
)
